# ELEKTRA-PMIC_v0_1-20240112.net
KiCad netlist of a schematic drawn in EAGLE
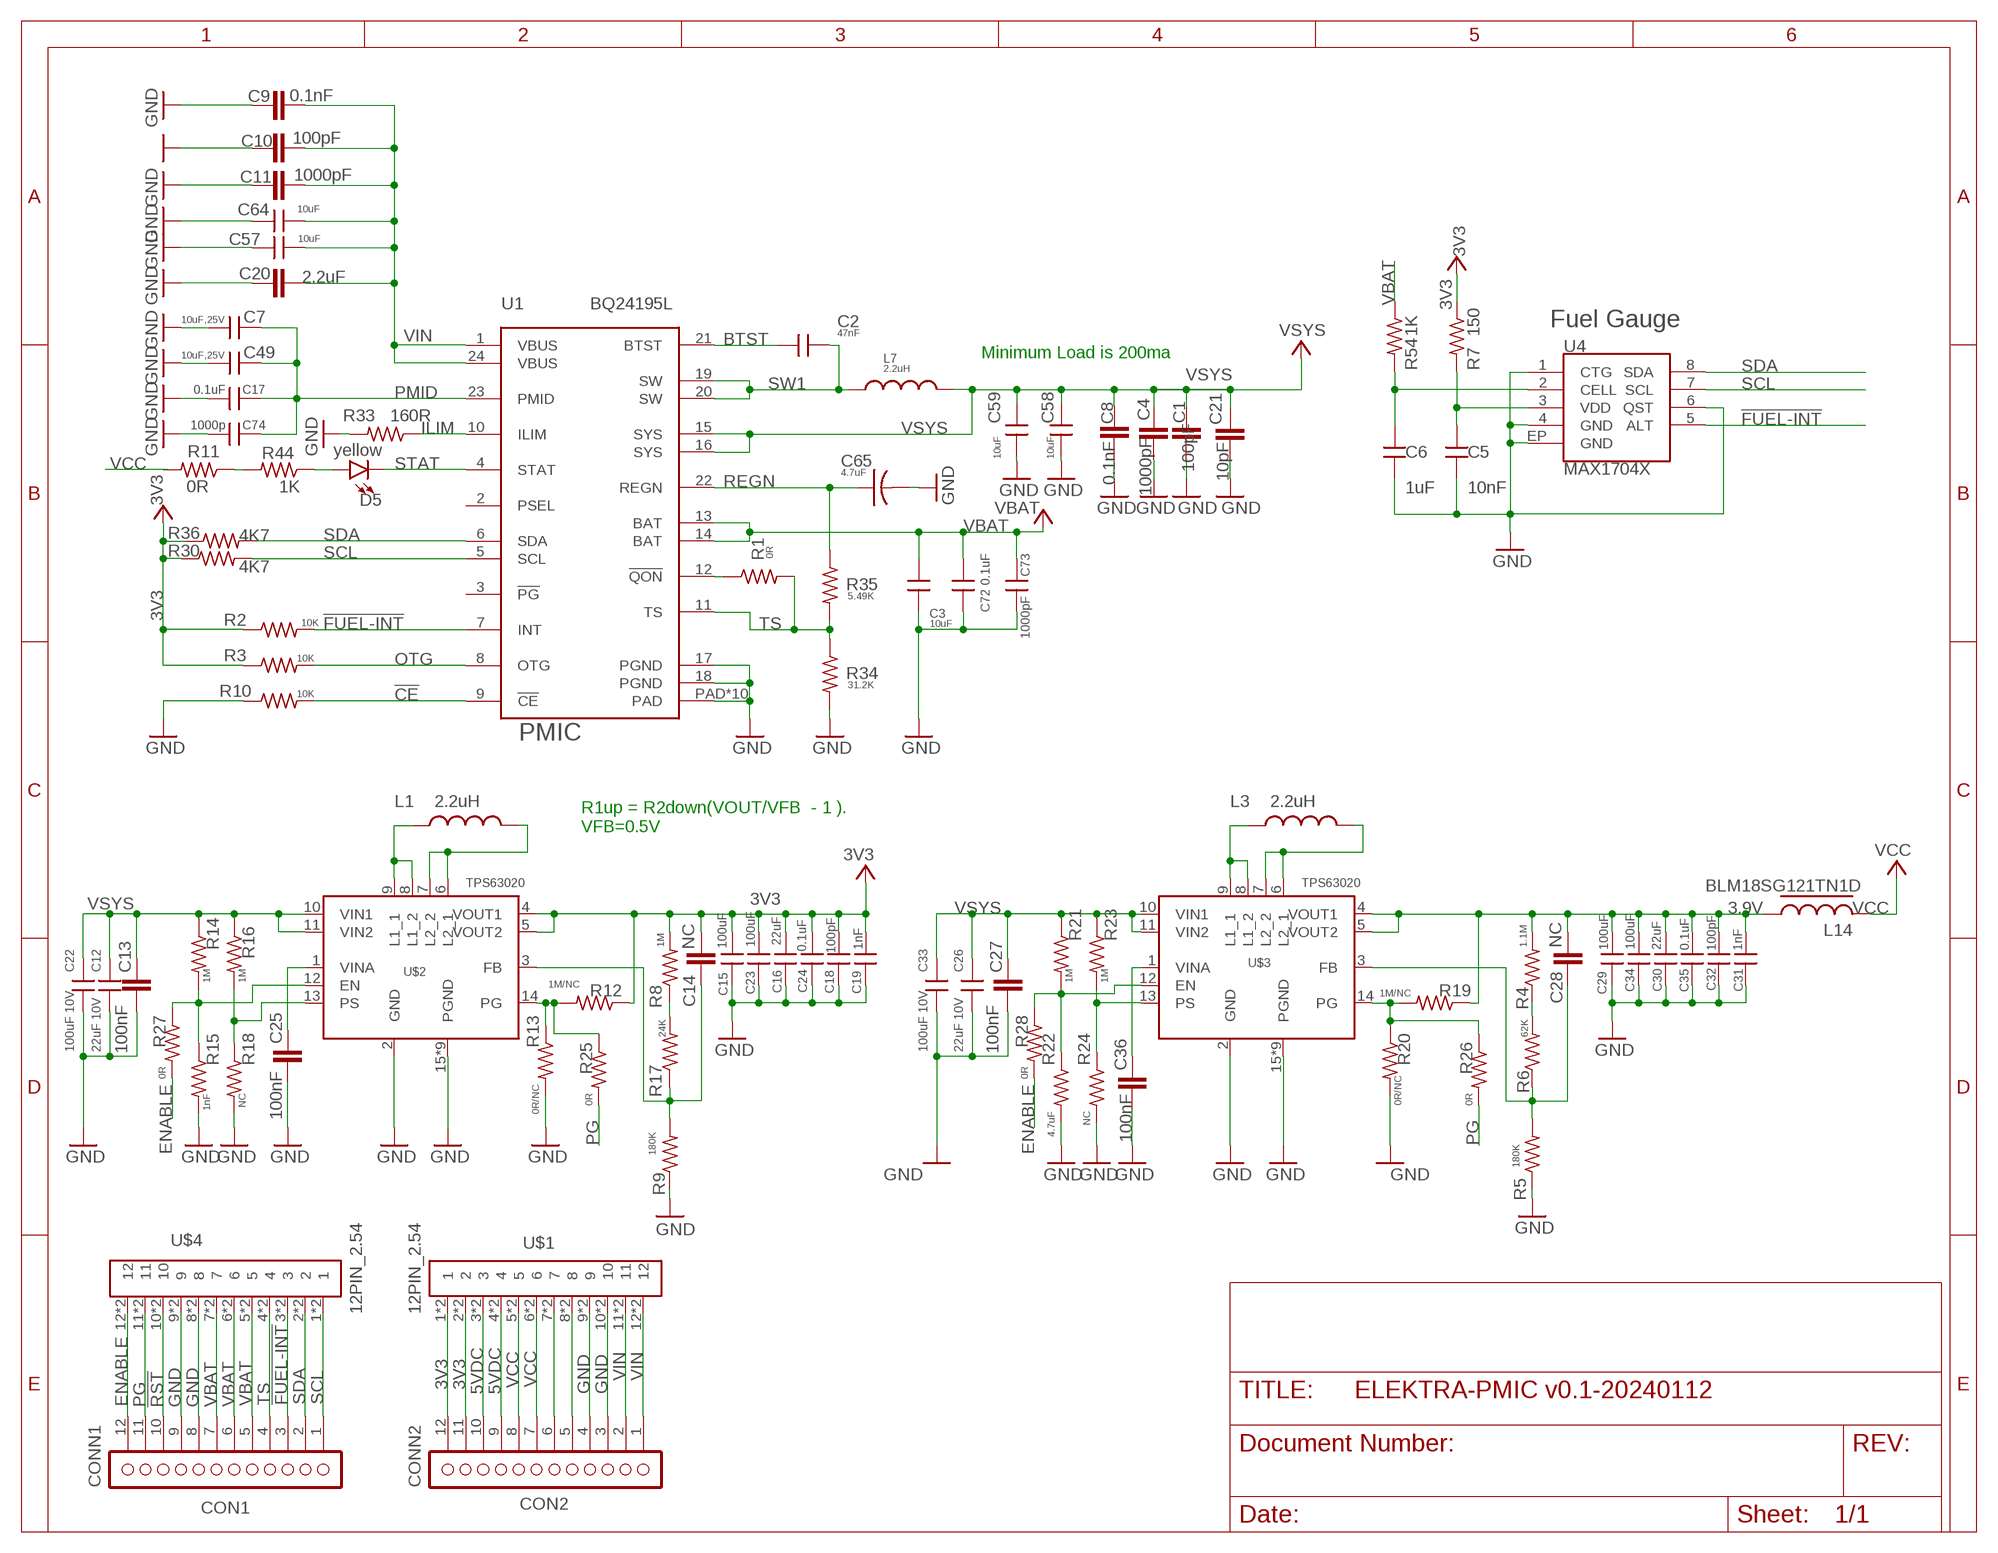
[diagram p0: schematic, sheet 1]

(export (version "E")
  (design (tool "Eeschema 10.0.6"))
  (components
    (comp (ref "C1")
      (value "100pF")
      (footprint "eagle-import:C0402_B")
      (libsource (lib "eagle-import") (part "CAP_1"))
    )
    (comp (ref "C2")
      (value "47nF")
      (footprint "eagle-import:C-0402")
      (libsource (lib "eagle-import") (part "particle SZ_CAP0402"))
    )
    (comp (ref "C3")
      (value "10uF")
      (footprint "eagle-import:C0603")
      (libsource (lib "eagle-import") (part "particle SZ_CAPC0603"))
    )
    (comp (ref "C4")
      (value "1000pF")
      (footprint "eagle-import:C0402_B")
      (libsource (lib "eagle-import") (part "CAP_1"))
    )
    (comp (ref "C5")
      (value "10nF")
      (footprint "eagle-import:C0402")
      (libsource (lib "eagle-import") (part "particle SZ_CAP0402A"))
    )
    (comp (ref "C6")
      (value "1uF")
      (footprint "eagle-import:C0402")
      (libsource (lib "eagle-import") (part "particle SZ_CAP0402A"))
    )
    (comp (ref "C7")
      (value "10uF,25V")
      (footprint "eagle-import:C-0603A")
      (libsource (lib "eagle-import") (part "particle SZ_CAP0603A"))
    )
    (comp (ref "C8")
      (value "0.1nF")
      (footprint "eagle-import:C0402_B")
      (libsource (lib "eagle-import") (part "CAP_1"))
    )
    (comp (ref "C9")
      (value "0.1nF")
      (footprint "eagle-import:C0402_B")
      (libsource (lib "eagle-import") (part "CAP_1"))
    )
    (comp (ref "C10")
      (value "100pF")
      (footprint "eagle-import:C0402_B")
      (libsource (lib "eagle-import") (part "CAP_1"))
    )
    (comp (ref "C11")
      (value "1000pF")
      (footprint "eagle-import:C0402_B")
      (libsource (lib "eagle-import") (part "CAP_1"))
    )
    (comp (ref "C12")
      (value "22uF 10V")
      (footprint "eagle-import:C0805")
      (libsource (lib "eagle-import") (part "particle SZ_21650216_CAPC0805"))
    )
    (comp (ref "C13")
      (value "100nF")
      (footprint "eagle-import:C0402_B")
      (libsource (lib "eagle-import") (part "CAP_1"))
    )
    (comp (ref "C14")
      (value "NC")
      (footprint "eagle-import:C0402_B")
      (libsource (lib "eagle-import") (part "CAP_1"))
    )
    (comp (ref "C15")
      (value "100uF")
      (footprint "eagle-import:C1206")
      (libsource (lib "eagle-import") (part "particle SZ_21650216_CAPC1206"))
    )
    (comp (ref "C16")
      (value "22uF")
      (footprint "eagle-import:C-0603A")
      (libsource (lib "eagle-import") (part "particle SZ_21650216_CAP0603A"))
    )
    (comp (ref "C17")
      (value "0.1uF")
      (footprint "eagle-import:C0402")
      (libsource (lib "eagle-import") (part "CAP0402A"))
    )
    (comp (ref "C18")
      (value "100pF")
      (footprint "eagle-import:C0402")
      (libsource (lib "eagle-import") (part "particle SZ_CAP0402A"))
    )
    (comp (ref "C19")
      (value "1nF")
      (footprint "eagle-import:C0402")
      (libsource (lib "eagle-import") (part "particle SZ_CAP0402A"))
    )
    (comp (ref "C20")
      (value "2.2uF")
      (footprint "eagle-import:C0402_B")
      (libsource (lib "eagle-import") (part "CAP_1"))
    )
    (comp (ref "C21")
      (value "10pF")
      (footprint "eagle-import:C0402_B")
      (libsource (lib "eagle-import") (part "CAP_1"))
    )
    (comp (ref "C22")
      (value "100uF 10V")
      (footprint "eagle-import:C1206")
      (libsource (lib "eagle-import") (part "particle SZ_21650216_CAPC1206"))
    )
    (comp (ref "C23")
      (value "100uF")
      (footprint "eagle-import:C1206")
      (libsource (lib "eagle-import") (part "particle SZ_21650216_CAPC1206"))
    )
    (comp (ref "C24")
      (value "0.1uF")
      (footprint "eagle-import:C0402")
      (libsource (lib "eagle-import") (part "particle SZ_CAP0402A"))
    )
    (comp (ref "C25")
      (value "100nF")
      (footprint "eagle-import:C0402_B")
      (libsource (lib "eagle-import") (part "CAP_1"))
    )
    (comp (ref "C26")
      (value "22uF 10V")
      (footprint "eagle-import:C0805")
      (libsource (lib "eagle-import") (part "particle SZ_21650216_CAPC0805"))
    )
    (comp (ref "C27")
      (value "100nF")
      (footprint "eagle-import:C0402_B")
      (libsource (lib "eagle-import") (part "CAP_1"))
    )
    (comp (ref "C28")
      (value "NC")
      (footprint "eagle-import:C0402_B")
      (libsource (lib "eagle-import") (part "CAP_1"))
    )
    (comp (ref "C29")
      (value "100uF")
      (footprint "eagle-import:C1206")
      (libsource (lib "eagle-import") (part "particle SZ_21650216_CAPC1206"))
    )
    (comp (ref "C30")
      (value "22uF")
      (footprint "eagle-import:C-0603A")
      (libsource (lib "eagle-import") (part "particle SZ_21650216_CAP0603A"))
    )
    (comp (ref "C31")
      (value "1nF")
      (footprint "eagle-import:C0402")
      (libsource (lib "eagle-import") (part "particle SZ_CAP0402A"))
    )
    (comp (ref "C32")
      (value "100pF")
      (footprint "eagle-import:C0402")
      (libsource (lib "eagle-import") (part "particle SZ_CAP0402A"))
    )
    (comp (ref "C33")
      (value "100uF 10V")
      (footprint "eagle-import:C1206")
      (libsource (lib "eagle-import") (part "particle SZ_21650216_CAPC1206"))
    )
    (comp (ref "C34")
      (value "100uF")
      (footprint "eagle-import:C1206")
      (libsource (lib "eagle-import") (part "particle SZ_21650216_CAPC1206"))
    )
    (comp (ref "C35")
      (value "0.1uF")
      (footprint "eagle-import:C0402")
      (libsource (lib "eagle-import") (part "particle SZ_CAP0402A"))
    )
    (comp (ref "C36")
      (value "100nF")
      (footprint "eagle-import:C0402_B")
      (libsource (lib "eagle-import") (part "CAP_1"))
    )
    (comp (ref "C49")
      (value "10uF,25V")
      (footprint "eagle-import:C-0603A")
      (libsource (lib "eagle-import") (part "particle SZ_CAP0603A"))
    )
    (comp (ref "C57")
      (value "10uF")
      (footprint "eagle-import:C-0603A")
      (libsource (lib "eagle-import") (part "particle SZ_CAP0603A"))
    )
    (comp (ref "C58")
      (value "10uF")
      (footprint "eagle-import:C-0603A")
      (libsource (lib "eagle-import") (part "particle SZ_CAP0603A"))
    )
    (comp (ref "C59")
      (value "10uF")
      (footprint "eagle-import:C-0603A")
      (libsource (lib "eagle-import") (part "particle SZ_CAP0603A"))
    )
    (comp (ref "C64")
      (value "10uF")
      (footprint "eagle-import:C-0603A")
      (libsource (lib "eagle-import") (part "particle SZ_CAP0603A"))
    )
    (comp (ref "C65")
      (value "4.7uF")
      (footprint "eagle-import:C0603_B")
      (libsource (lib "eagle-import") (part "C-US0603"))
    )
    (comp (ref "C72")
      (value "0.1uF")
      (footprint "eagle-import:C-0402")
      (libsource (lib "eagle-import") (part "particle SZ_CAP0402"))
    )
    (comp (ref "C73")
      (value "1000pF")
      (footprint "eagle-import:C-0402")
      (libsource (lib "eagle-import") (part "particle SZ_CAP0402"))
    )
    (comp (ref "C74")
      (value "1000p")
      (footprint "eagle-import:C-0402")
      (libsource (lib "eagle-import") (part "particle SZ_CAP0402"))
    )
    (comp (ref "CONN1")
      (value "CON1")
      (footprint "eagle-import:1X12_SMD_STRAIGHT")
      (libsource (lib "eagle-import") (part "CONN12"))
    )
    (comp (ref "CONN2")
      (value "CON2")
      (footprint "eagle-import:1X12_SMD_STRAIGHT")
      (libsource (lib "eagle-import") (part "CONN12"))
    )
    (comp (ref "D5")
      (value "yellow")
      (footprint "eagle-import:LED-0603")
      (libsource (lib "eagle-import") (part "LED-RED0603"))
    )
    (comp (ref "L1")
      (value "2.2uH")
      (footprint "eagle-import:INDUCTOR-VLS-E")
      (libsource (lib "eagle-import") (part "INDUCTOR-SPARKFUNVLS3012ET-4R7M"))
    )
    (comp (ref "L3")
      (value "2.2uH")
      (footprint "eagle-import:INDUCTOR-VLS-E")
      (libsource (lib "eagle-import") (part "INDUCTOR-SPARKFUNVLS3012ET-4R7M"))
    )
    (comp (ref "L7")
      (value "2.2uH")
      (footprint "eagle-import:INDUCTOR-4040")
      (libsource (lib "eagle-import") (part "INDUCTORI"))
    )
    (comp (ref "L14")
      (value "BLM18SG121TN1D")
      (footprint "eagle-import:R-0603A")
      (libsource (lib "eagle-import") (part "L"))
    )
    (comp (ref "R1")
      (value "0R")
      (footprint "eagle-import:R0402_B")
      (libsource (lib "eagle-import") (part "Spark_R-US_"))
    )
    (comp (ref "R2")
      (value "10K")
      (footprint "eagle-import:R0402_B")
      (libsource (lib "eagle-import") (part "Spark_R-US_"))
    )
    (comp (ref "R3")
      (value "10K")
      (footprint "eagle-import:R0402_B")
      (libsource (lib "eagle-import") (part "Spark_R-US_"))
    )
    (comp (ref "R4")
      (value "1.1M")
      (footprint "eagle-import:R0402_B")
      (libsource (lib "eagle-import") (part "Spark_R-US_"))
    )
    (comp (ref "R5")
      (value "180K")
      (footprint "eagle-import:R0402_B")
      (libsource (lib "eagle-import") (part "Spark_R-US_"))
    )
    (comp (ref "R6")
      (value "62K")
      (footprint "eagle-import:R0402_B")
      (libsource (lib "eagle-import") (part "Spark_R-US_"))
    )
    (comp (ref "R7")
      (value "150")
      (footprint "eagle-import:R0402_B")
      (libsource (lib "eagle-import") (part "R-US_"))
    )
    (comp (ref "R8")
      (value "1M")
      (footprint "eagle-import:R0402_B")
      (libsource (lib "eagle-import") (part "Spark_R-US_"))
    )
    (comp (ref "R9")
      (value "180K")
      (footprint "eagle-import:R0402_B")
      (libsource (lib "eagle-import") (part "Spark_R-US_"))
    )
    (comp (ref "R10")
      (value "10K")
      (footprint "eagle-import:R0402_B")
      (libsource (lib "eagle-import") (part "Spark_R-US_"))
    )
    (comp (ref "R11")
      (value "0R")
      (footprint "eagle-import:R0402_B")
      (libsource (lib "eagle-import") (part "R-US_"))
    )
    (comp (ref "R12")
      (value "1M/NC")
      (footprint "eagle-import:R0402_B")
      (libsource (lib "eagle-import") (part "Spark_R-US_"))
    )
    (comp (ref "R13")
      (value "0R/NC")
      (footprint "eagle-import:R0402_B")
      (libsource (lib "eagle-import") (part "Spark_R-US_"))
    )
    (comp (ref "R14")
      (value "1M")
      (footprint "eagle-import:R0402_B")
      (libsource (lib "eagle-import") (part "Spark_R-US_"))
    )
    (comp (ref "R15")
      (value "1nF")
      (footprint "eagle-import:R0402_B")
      (libsource (lib "eagle-import") (part "Spark_R-US_"))
    )
    (comp (ref "R16")
      (value "1M")
      (footprint "eagle-import:R0402_B")
      (libsource (lib "eagle-import") (part "Spark_R-US_"))
    )
    (comp (ref "R17")
      (value "24K")
      (footprint "eagle-import:R0402_B")
      (libsource (lib "eagle-import") (part "Spark_R-US_"))
    )
    (comp (ref "R18")
      (value "NC")
      (footprint "eagle-import:R0402_B")
      (libsource (lib "eagle-import") (part "Spark_R-US_"))
    )
    (comp (ref "R19")
      (value "1M/NC")
      (footprint "eagle-import:R0402_B")
      (libsource (lib "eagle-import") (part "Spark_R-US_"))
    )
    (comp (ref "R20")
      (value "0R/NC")
      (footprint "eagle-import:R0402_B")
      (libsource (lib "eagle-import") (part "Spark_R-US_"))
    )
    (comp (ref "R21")
      (value "1M")
      (footprint "eagle-import:R0402_B")
      (libsource (lib "eagle-import") (part "Spark_R-US_"))
    )
    (comp (ref "R22")
      (value "4.7uF")
      (footprint "eagle-import:R0402_B")
      (libsource (lib "eagle-import") (part "Spark_R-US_"))
    )
    (comp (ref "R23")
      (value "1M")
      (footprint "eagle-import:R0402_B")
      (libsource (lib "eagle-import") (part "Spark_R-US_"))
    )
    (comp (ref "R24")
      (value "NC")
      (footprint "eagle-import:R0402_B")
      (libsource (lib "eagle-import") (part "Spark_R-US_"))
    )
    (comp (ref "R25")
      (value "0R")
      (footprint "eagle-import:R0402_B")
      (libsource (lib "eagle-import") (part "Spark_R-US_"))
    )
    (comp (ref "R26")
      (value "0R")
      (footprint "eagle-import:R0402_B")
      (libsource (lib "eagle-import") (part "Spark_R-US_"))
    )
    (comp (ref "R27")
      (value "0R")
      (footprint "eagle-import:R0402_B")
      (libsource (lib "eagle-import") (part "Spark_R-US_"))
    )
    (comp (ref "R28")
      (value "0R")
      (footprint "eagle-import:R0402_B")
      (libsource (lib "eagle-import") (part "Spark_R-US_"))
    )
    (comp (ref "R30")
      (value "4K7")
      (footprint "eagle-import:R0402_B")
      (libsource (lib "eagle-import") (part "R-US_"))
    )
    (comp (ref "R33")
      (value "160R")
      (footprint "eagle-import:R0402_B")
      (libsource (lib "eagle-import") (part "R-US_"))
    )
    (comp (ref "R34")
      (value "31.2K")
      (footprint "eagle-import:R0402_B")
      (libsource (lib "eagle-import") (part "Spark_R-US_"))
    )
    (comp (ref "R35")
      (value "5.49K")
      (footprint "eagle-import:R0402_B")
      (libsource (lib "eagle-import") (part "Spark_R-US_"))
    )
    (comp (ref "R36")
      (value "4K7")
      (footprint "eagle-import:R0402_B")
      (libsource (lib "eagle-import") (part "R-US_"))
    )
    (comp (ref "R44")
      (value "1K")
      (footprint "eagle-import:R0402_B")
      (libsource (lib "eagle-import") (part "R-US_"))
    )
    (comp (ref "R54")
      (value "1K")
      (footprint "eagle-import:R0402_B")
      (libsource (lib "eagle-import") (part "R-US_"))
    )
    (comp (ref "U$1")
      (value "12PIN_2.54")
      (footprint "eagle-import:12PIN_2.54")
      (libsource (lib "eagle-import") (part "12PIN_2.54"))
    )
    (comp (ref "U$2")
      (value "TPS63020")
      (footprint "eagle-import:TPS63020")
      (libsource (lib "eagle-import") (part "TPS63020"))
    )
    (comp (ref "U$3")
      (value "TPS63020")
      (footprint "eagle-import:TPS63020")
      (libsource (lib "eagle-import") (part "TPS63020"))
    )
    (comp (ref "U$4")
      (value "12PIN_2.54")
      (footprint "eagle-import:12PIN_2.54")
      (libsource (lib "eagle-import") (part "12PIN_2.54"))
    )
    (comp (ref "U1")
      (value "BQ24195L")
      (footprint "eagle-import:QFN24")
      (libsource (lib "eagle-import") (part "BQ24298RTWR"))
    )
    (comp (ref "U4")
      (value "MAX1704X")
      (footprint "eagle-import:TDFN-8")
      (libsource (lib "eagle-import") (part "MAX1704X"))
    )
  )
  (nets
    (net (code "1") (name "/3.9V") (class "Default")
      (node (ref "C28") (pin "2") (pinfunction "P$2_2") (pintype "passive"))
      (node (ref "C29") (pin "1") (pinfunction "1_1") (pintype "bidirectional"))
      (node (ref "C30") (pin "1") (pinfunction "1_1") (pintype "bidirectional"))
      (node (ref "C31") (pin "1") (pinfunction "1_1") (pintype "bidirectional"))
      (node (ref "C32") (pin "1") (pinfunction "1_1") (pintype "bidirectional"))
      (node (ref "C34") (pin "1") (pinfunction "1_1") (pintype "bidirectional"))
      (node (ref "C35") (pin "1") (pinfunction "1_1") (pintype "bidirectional"))
      (node (ref "L14") (pin "2") (pinfunction "2_2") (pintype "bidirectional"))
      (node (ref "R19") (pin "1") (pinfunction "1_1") (pintype "passive"))
      (node (ref "R4") (pin "2") (pinfunction "2_2") (pintype "passive"))
      (node (ref "U$3") (pin "4") (pinfunction "VOUT1_4") (pintype "bidirectional"))
      (node (ref "U$3") (pin "5") (pinfunction "VOUT2_5") (pintype "bidirectional"))
    )
    (net (code "2") (name "/5VDC") (class "Default")
      (node (ref "CONN2") (pin "10") (pinfunction "10_10") (pintype "passive"))
      (node (ref "CONN2") (pin "9") (pinfunction "9_9") (pintype "passive"))
      (node (ref "U$1") (pin "3") (pinfunction "3_3") (pintype "bidirectional"))
      (node (ref "U$1") (pin "4") (pinfunction "4_4") (pintype "bidirectional"))
      (node (ref "U$1") (pin "P$3") (pinfunction "3_P$3") (pintype "bidirectional"))
      (node (ref "U$1") (pin "P$4") (pinfunction "4_P$4") (pintype "bidirectional"))
    )
    (net (code "3") (name "/BTST") (class "Default")
      (node (ref "C2") (pin "1") (pinfunction "1_1") (pintype "bidirectional"))
      (node (ref "U1") (pin "21") (pinfunction "BTST_21") (pintype "bidirectional"))
    )
    (net (code "4") (name "/ENABLE") (class "Default")
      (node (ref "CONN1") (pin "12") (pinfunction "12_12") (pintype "passive"))
      (node (ref "R27") (pin "2") (pinfunction "2_2") (pintype "passive"))
      (node (ref "R28") (pin "2") (pinfunction "2_2") (pintype "passive"))
      (node (ref "U$4") (pin "12") (pinfunction "12_12") (pintype "bidirectional"))
      (node (ref "U$4") (pin "P$12") (pinfunction "12_P$12") (pintype "bidirectional"))
    )
    (net (code "5") (name "/ILIM") (class "Default")
      (node (ref "R33") (pin "1") (pinfunction "1_1") (pintype "passive"))
      (node (ref "U1") (pin "10") (pinfunction "ILIM_10") (pintype "output"))
    )
    (net (code "6") (name "/OTG") (class "Default")
      (node (ref "R3") (pin "2") (pinfunction "2_2") (pintype "passive"))
      (node (ref "U1") (pin "8") (pinfunction "OTG_8") (pintype "bidirectional"))
    )
    (net (code "7") (name "/PG") (class "Default")
      (node (ref "CONN1") (pin "11") (pinfunction "11_11") (pintype "passive"))
      (node (ref "R25") (pin "2") (pinfunction "2_2") (pintype "passive"))
      (node (ref "R26") (pin "2") (pinfunction "2_2") (pintype "passive"))
      (node (ref "U$4") (pin "11") (pinfunction "11_11") (pintype "bidirectional"))
      (node (ref "U$4") (pin "P$11") (pinfunction "11_P$11") (pintype "bidirectional"))
    )
    (net (code "8") (name "/PMID") (class "Default")
      (node (ref "C17") (pin "2") (pinfunction "2_2") (pintype "bidirectional"))
      (node (ref "C49") (pin "1") (pinfunction "1_1") (pintype "bidirectional"))
      (node (ref "C7") (pin "1") (pinfunction "1_1") (pintype "bidirectional"))
      (node (ref "C74") (pin "2") (pinfunction "2_2") (pintype "bidirectional"))
      (node (ref "U1") (pin "23") (pinfunction "PMID_23") (pintype "passive"))
    )
    (net (code "9") (name "/REGN") (class "Default")
      (node (ref "C65") (pin "1") (pinfunction "1_1") (pintype "passive"))
      (node (ref "R35") (pin "1") (pinfunction "1_1") (pintype "passive"))
      (node (ref "U1") (pin "22") (pinfunction "REGN_22") (pintype "bidirectional"))
    )
    (net (code "10") (name "/SCL") (class "Default")
      (node (ref "CONN1") (pin "1") (pinfunction "1_1") (pintype "passive"))
      (node (ref "R30") (pin "2") (pinfunction "2_2") (pintype "passive"))
      (node (ref "U$4") (pin "1") (pinfunction "1_1") (pintype "bidirectional"))
      (node (ref "U$4") (pin "P$1") (pinfunction "1_P$1") (pintype "bidirectional"))
      (node (ref "U1") (pin "5") (pinfunction "SCL_5") (pintype "output"))
      (node (ref "U4") (pin "7") (pinfunction "SCL_7") (pintype "bidirectional"))
    )
    (net (code "11") (name "/SDA") (class "Default")
      (node (ref "CONN1") (pin "2") (pinfunction "2_2") (pintype "passive"))
      (node (ref "R36") (pin "2") (pinfunction "2_2") (pintype "passive"))
      (node (ref "U$4") (pin "2") (pinfunction "2_2") (pintype "bidirectional"))
      (node (ref "U$4") (pin "P$2") (pinfunction "2_P$2") (pintype "bidirectional"))
      (node (ref "U1") (pin "6") (pinfunction "SDA_6") (pintype "bidirectional"))
      (node (ref "U4") (pin "8") (pinfunction "SDA_8") (pintype "bidirectional"))
    )
    (net (code "12") (name "/STAT") (class "Default")
      (node (ref "D5") (pin "C") (pinfunction "C_C") (pintype "passive"))
      (node (ref "U1") (pin "4") (pinfunction "STAT_4") (pintype "bidirectional"))
    )
    (net (code "13") (name "/SW1") (class "Default")
      (node (ref "C2") (pin "2") (pinfunction "2_2") (pintype "bidirectional"))
      (node (ref "L7") (pin "P$1") (pinfunction "1_P$1") (pintype "passive"))
      (node (ref "U1") (pin "19") (pinfunction "SW_19") (pintype "power_in"))
      (node (ref "U1") (pin "20") (pinfunction "SW_20") (pintype "power_in"))
    )
    (net (code "14") (name "/TS") (class "Default")
      (node (ref "CONN1") (pin "4") (pinfunction "4_4") (pintype "passive"))
      (node (ref "R1") (pin "2") (pinfunction "2_2") (pintype "passive"))
      (node (ref "R34") (pin "1") (pinfunction "1_1") (pintype "passive"))
      (node (ref "R35") (pin "2") (pinfunction "2_2") (pintype "passive"))
      (node (ref "U$4") (pin "4") (pinfunction "4_4") (pintype "bidirectional"))
      (node (ref "U$4") (pin "P$4") (pinfunction "4_P$4") (pintype "bidirectional"))
      (node (ref "U1") (pin "11") (pinfunction "TS_11") (pintype "bidirectional"))
    )
    (net (code "15") (name "/VIN") (class "Default")
      (node (ref "C10") (pin "2") (pinfunction "P$2_2") (pintype "passive"))
      (node (ref "C11") (pin "2") (pinfunction "P$2_2") (pintype "passive"))
      (node (ref "C20") (pin "2") (pinfunction "P$2_2") (pintype "passive"))
      (node (ref "C57") (pin "1") (pinfunction "1_1") (pintype "bidirectional"))
      (node (ref "C64") (pin "1") (pinfunction "1_1") (pintype "bidirectional"))
      (node (ref "C9") (pin "2") (pinfunction "P$2_2") (pintype "passive"))
      (node (ref "CONN2") (pin "1") (pinfunction "1_1") (pintype "passive"))
      (node (ref "CONN2") (pin "2") (pinfunction "2_2") (pintype "passive"))
      (node (ref "U$1") (pin "11") (pinfunction "11_11") (pintype "bidirectional"))
      (node (ref "U$1") (pin "12") (pinfunction "12_12") (pintype "bidirectional"))
      (node (ref "U$1") (pin "P$11") (pinfunction "11_P$11") (pintype "bidirectional"))
      (node (ref "U$1") (pin "P$12") (pinfunction "12_P$12") (pintype "bidirectional"))
      (node (ref "U1") (pin "1") (pinfunction "VBUS_1") (pintype "power_in"))
      (node (ref "U1") (pin "24") (pinfunction "VBUS_24") (pintype "passive"))
    )
    (net (code "16") (name "/~{CE}") (class "Default")
      (node (ref "R10") (pin "2") (pinfunction "2_2") (pintype "passive"))
      (node (ref "U1") (pin "9") (pinfunction "~{CE}_9") (pintype "output"))
    )
    (net (code "17") (name "/~{FUEL-INT}") (class "Default")
      (node (ref "CONN1") (pin "3") (pinfunction "3_3") (pintype "passive"))
      (node (ref "R2") (pin "2") (pinfunction "2_2") (pintype "passive"))
      (node (ref "U$4") (pin "3") (pinfunction "3_3") (pintype "bidirectional"))
      (node (ref "U$4") (pin "P$3") (pinfunction "3_P$3") (pintype "bidirectional"))
      (node (ref "U1") (pin "7") (pinfunction "INT_7") (pintype "bidirectional"))
      (node (ref "U4") (pin "5") (pinfunction "ALT_5") (pintype "bidirectional"))
    )
    (net (code "18") (name "/~{RST}") (class "Default")
      (node (ref "CONN1") (pin "10") (pinfunction "10_10") (pintype "passive"))
      (node (ref "U$4") (pin "10") (pinfunction "10_10") (pintype "bidirectional"))
      (node (ref "U$4") (pin "P$10") (pinfunction "10_P$10") (pintype "bidirectional"))
    )
    (net (code "19") (name "3V3") (class "Default")
      (node (ref "C14") (pin "2") (pinfunction "P$2_2") (pintype "passive"))
      (node (ref "C15") (pin "1") (pinfunction "1_1") (pintype "bidirectional"))
      (node (ref "C16") (pin "1") (pinfunction "1_1") (pintype "bidirectional"))
      (node (ref "C18") (pin "1") (pinfunction "1_1") (pintype "bidirectional"))
      (node (ref "C19") (pin "1") (pinfunction "1_1") (pintype "bidirectional"))
      (node (ref "C23") (pin "1") (pinfunction "1_1") (pintype "bidirectional"))
      (node (ref "C24") (pin "1") (pinfunction "1_1") (pintype "bidirectional"))
      (node (ref "CONN2") (pin "11") (pinfunction "11_11") (pintype "passive"))
      (node (ref "CONN2") (pin "12") (pinfunction "12_12") (pintype "passive"))
      (node (ref "R12") (pin "1") (pinfunction "1_1") (pintype "passive"))
      (node (ref "R2") (pin "1") (pinfunction "1_1") (pintype "passive"))
      (node (ref "R3") (pin "1") (pinfunction "1_1") (pintype "passive"))
      (node (ref "R30") (pin "1") (pinfunction "1_1") (pintype "passive"))
      (node (ref "R36") (pin "1") (pinfunction "1_1") (pintype "passive"))
      (node (ref "R7") (pin "1") (pinfunction "1_1") (pintype "passive"))
      (node (ref "R8") (pin "2") (pinfunction "2_2") (pintype "passive"))
      (node (ref "U$1") (pin "1") (pinfunction "1_1") (pintype "bidirectional"))
      (node (ref "U$1") (pin "2") (pinfunction "2_2") (pintype "bidirectional"))
      (node (ref "U$1") (pin "P$1") (pinfunction "1_P$1") (pintype "bidirectional"))
      (node (ref "U$1") (pin "P$2") (pinfunction "2_P$2") (pintype "bidirectional"))
      (node (ref "U$2") (pin "4") (pinfunction "VOUT1_4") (pintype "bidirectional"))
      (node (ref "U$2") (pin "5") (pinfunction "VOUT2_5") (pintype "bidirectional"))
    )
    (net (code "20") (name "GND") (class "Default")
      (node (ref "C1") (pin "1") (pinfunction "P$1_1") (pintype "passive"))
      (node (ref "C10") (pin "1") (pinfunction "P$1_1") (pintype "passive"))
      (node (ref "C11") (pin "1") (pinfunction "P$1_1") (pintype "passive"))
      (node (ref "C12") (pin "2") (pinfunction "2_2") (pintype "bidirectional"))
      (node (ref "C13") (pin "1") (pinfunction "P$1_1") (pintype "passive"))
      (node (ref "C15") (pin "2") (pinfunction "2_2") (pintype "bidirectional"))
      (node (ref "C16") (pin "2") (pinfunction "2_2") (pintype "bidirectional"))
      (node (ref "C17") (pin "1") (pinfunction "1_1") (pintype "bidirectional"))
      (node (ref "C18") (pin "2") (pinfunction "2_2") (pintype "bidirectional"))
      (node (ref "C19") (pin "2") (pinfunction "2_2") (pintype "bidirectional"))
      (node (ref "C20") (pin "1") (pinfunction "P$1_1") (pintype "passive"))
      (node (ref "C21") (pin "1") (pinfunction "P$1_1") (pintype "passive"))
      (node (ref "C22") (pin "2") (pinfunction "2_2") (pintype "bidirectional"))
      (node (ref "C23") (pin "2") (pinfunction "2_2") (pintype "bidirectional"))
      (node (ref "C24") (pin "2") (pinfunction "2_2") (pintype "bidirectional"))
      (node (ref "C25") (pin "1") (pinfunction "P$1_1") (pintype "passive"))
      (node (ref "C26") (pin "2") (pinfunction "2_2") (pintype "bidirectional"))
      (node (ref "C27") (pin "1") (pinfunction "P$1_1") (pintype "passive"))
      (node (ref "C29") (pin "2") (pinfunction "2_2") (pintype "bidirectional"))
      (node (ref "C3") (pin "2") (pinfunction "2_2") (pintype "bidirectional"))
      (node (ref "C30") (pin "2") (pinfunction "2_2") (pintype "bidirectional"))
      (node (ref "C31") (pin "2") (pinfunction "2_2") (pintype "bidirectional"))
      (node (ref "C32") (pin "2") (pinfunction "2_2") (pintype "bidirectional"))
      (node (ref "C33") (pin "2") (pinfunction "2_2") (pintype "bidirectional"))
      (node (ref "C34") (pin "2") (pinfunction "2_2") (pintype "bidirectional"))
      (node (ref "C35") (pin "2") (pinfunction "2_2") (pintype "bidirectional"))
      (node (ref "C36") (pin "1") (pinfunction "P$1_1") (pintype "passive"))
      (node (ref "C4") (pin "1") (pinfunction "P$1_1") (pintype "passive"))
      (node (ref "C49") (pin "2") (pinfunction "2_2") (pintype "bidirectional"))
      (node (ref "C5") (pin "2") (pinfunction "2_2") (pintype "bidirectional"))
      (node (ref "C57") (pin "2") (pinfunction "2_2") (pintype "bidirectional"))
      (node (ref "C58") (pin "2") (pinfunction "2_2") (pintype "bidirectional"))
      (node (ref "C59") (pin "2") (pinfunction "2_2") (pintype "bidirectional"))
      (node (ref "C6") (pin "2") (pinfunction "2_2") (pintype "bidirectional"))
      (node (ref "C64") (pin "2") (pinfunction "2_2") (pintype "bidirectional"))
      (node (ref "C65") (pin "2") (pinfunction "2_2") (pintype "passive"))
      (node (ref "C7") (pin "2") (pinfunction "2_2") (pintype "bidirectional"))
      (node (ref "C72") (pin "2") (pinfunction "2_2") (pintype "bidirectional"))
      (node (ref "C73") (pin "2") (pinfunction "2_2") (pintype "bidirectional"))
      (node (ref "C74") (pin "1") (pinfunction "1_1") (pintype "bidirectional"))
      (node (ref "C8") (pin "1") (pinfunction "P$1_1") (pintype "passive"))
      (node (ref "C9") (pin "1") (pinfunction "P$1_1") (pintype "passive"))
      (node (ref "CONN1") (pin "8") (pinfunction "8_8") (pintype "passive"))
      (node (ref "CONN1") (pin "9") (pinfunction "9_9") (pintype "passive"))
      (node (ref "CONN2") (pin "3") (pinfunction "3_3") (pintype "passive"))
      (node (ref "CONN2") (pin "4") (pinfunction "4_4") (pintype "passive"))
      (node (ref "R10") (pin "1") (pinfunction "1_1") (pintype "passive"))
      (node (ref "R13") (pin "2") (pinfunction "2_2") (pintype "passive"))
      (node (ref "R15") (pin "2") (pinfunction "2_2") (pintype "passive"))
      (node (ref "R18") (pin "2") (pinfunction "2_2") (pintype "passive"))
      (node (ref "R20") (pin "2") (pinfunction "2_2") (pintype "passive"))
      (node (ref "R22") (pin "2") (pinfunction "2_2") (pintype "passive"))
      (node (ref "R24") (pin "2") (pinfunction "2_2") (pintype "passive"))
      (node (ref "R33") (pin "2") (pinfunction "2_2") (pintype "passive"))
      (node (ref "R34") (pin "2") (pinfunction "2_2") (pintype "passive"))
      (node (ref "R5") (pin "1") (pinfunction "1_1") (pintype "passive"))
      (node (ref "R9") (pin "1") (pinfunction "1_1") (pintype "passive"))
      (node (ref "U$1") (pin "10") (pinfunction "10_10") (pintype "bidirectional"))
      (node (ref "U$1") (pin "9") (pinfunction "9_9") (pintype "bidirectional"))
      (node (ref "U$1") (pin "P$10") (pinfunction "10_P$10") (pintype "bidirectional"))
      (node (ref "U$1") (pin "P$9") (pinfunction "9_P$9") (pintype "bidirectional"))
      (node (ref "U$2") (pin "15") (pinfunction "PGND_15") (pintype "bidirectional"))
      (node (ref "U$2") (pin "16") (pinfunction "PGND_16") (pintype "bidirectional"))
      (node (ref "U$2") (pin "17") (pinfunction "PGND_17") (pintype "bidirectional"))
      (node (ref "U$2") (pin "18") (pinfunction "PGND_18") (pintype "bidirectional"))
      (node (ref "U$2") (pin "19") (pinfunction "PGND_19") (pintype "bidirectional"))
      (node (ref "U$2") (pin "2") (pinfunction "GND_2") (pintype "bidirectional"))
      (node (ref "U$2") (pin "20") (pinfunction "PGND_20") (pintype "bidirectional"))
      (node (ref "U$2") (pin "21") (pinfunction "PGND_21") (pintype "bidirectional"))
      (node (ref "U$2") (pin "22") (pinfunction "PGND_22") (pintype "bidirectional"))
      (node (ref "U$2") (pin "23") (pinfunction "PGND_23") (pintype "bidirectional"))
      (node (ref "U$3") (pin "15") (pinfunction "PGND_15") (pintype "bidirectional"))
      (node (ref "U$3") (pin "16") (pinfunction "PGND_16") (pintype "bidirectional"))
      (node (ref "U$3") (pin "17") (pinfunction "PGND_17") (pintype "bidirectional"))
      (node (ref "U$3") (pin "18") (pinfunction "PGND_18") (pintype "bidirectional"))
      (node (ref "U$3") (pin "19") (pinfunction "PGND_19") (pintype "bidirectional"))
      (node (ref "U$3") (pin "2") (pinfunction "GND_2") (pintype "bidirectional"))
      (node (ref "U$3") (pin "20") (pinfunction "PGND_20") (pintype "bidirectional"))
      (node (ref "U$3") (pin "21") (pinfunction "PGND_21") (pintype "bidirectional"))
      (node (ref "U$3") (pin "22") (pinfunction "PGND_22") (pintype "bidirectional"))
      (node (ref "U$3") (pin "23") (pinfunction "PGND_23") (pintype "bidirectional"))
      (node (ref "U$4") (pin "8") (pinfunction "8_8") (pintype "bidirectional"))
      (node (ref "U$4") (pin "9") (pinfunction "9_9") (pintype "bidirectional"))
      (node (ref "U$4") (pin "P$8") (pinfunction "8_P$8") (pintype "bidirectional"))
      (node (ref "U$4") (pin "P$9") (pinfunction "9_P$9") (pintype "bidirectional"))
      (node (ref "U1") (pin "17") (pinfunction "PGND_17") (pintype "passive"))
      (node (ref "U1") (pin "18") (pinfunction "PGND_18") (pintype "passive"))
      (node (ref "U1") (pin "PAD") (pinfunction "PAD_PAD") (pintype "power_in"))
      (node (ref "U1") (pin "PAD@1") (pinfunction "PAD_PAD@1") (pintype "power_in"))
      (node (ref "U1") (pin "PAD@2") (pinfunction "PAD_PAD@2") (pintype "power_in"))
      (node (ref "U1") (pin "PAD@3") (pinfunction "PAD_PAD@3") (pintype "power_in"))
      (node (ref "U1") (pin "PAD@4") (pinfunction "PAD_PAD@4") (pintype "power_in"))
      (node (ref "U1") (pin "PAD@5") (pinfunction "PAD_PAD@5") (pintype "power_in"))
      (node (ref "U1") (pin "PAD@6") (pinfunction "PAD_PAD@6") (pintype "power_in"))
      (node (ref "U1") (pin "PAD@7") (pinfunction "PAD_PAD@7") (pintype "power_in"))
      (node (ref "U1") (pin "PAD@8") (pinfunction "PAD_PAD@8") (pintype "power_in"))
      (node (ref "U1") (pin "PAD@9") (pinfunction "PAD_PAD@9") (pintype "power_in"))
      (node (ref "U4") (pin "1") (pinfunction "CTG_1") (pintype "bidirectional"))
      (node (ref "U4") (pin "4") (pinfunction "GND_4") (pintype "bidirectional"))
      (node (ref "U4") (pin "6") (pinfunction "QST_6") (pintype "bidirectional"))
      (node (ref "U4") (pin "EP") (pinfunction "GND_EP") (pintype "bidirectional"))
    )
    (net (code "21") (name "Net-(C14-P$1)") (class "Default")
      (node (ref "C14") (pin "1") (pinfunction "P$1_1") (pintype "passive"))
      (node (ref "R17") (pin "1") (pinfunction "1_1") (pintype "passive"))
      (node (ref "R9") (pin "2") (pinfunction "2_2") (pintype "passive"))
      (node (ref "U$2") (pin "3") (pinfunction "FB_3") (pintype "bidirectional"))
    )
    (net (code "22") (name "Net-(C25-P$2)") (class "Default")
      (node (ref "C25") (pin "2") (pinfunction "P$2_2") (pintype "passive"))
      (node (ref "U$2") (pin "1") (pinfunction "VINA_1") (pintype "bidirectional"))
    )
    (net (code "23") (name "Net-(C28-P$1)") (class "Default")
      (node (ref "C28") (pin "1") (pinfunction "P$1_1") (pintype "passive"))
      (node (ref "R5") (pin "2") (pinfunction "2_2") (pintype "passive"))
      (node (ref "R6") (pin "1") (pinfunction "1_1") (pintype "passive"))
      (node (ref "U$3") (pin "3") (pinfunction "FB_3") (pintype "bidirectional"))
    )
    (net (code "24") (name "Net-(C36-P$2)") (class "Default")
      (node (ref "C36") (pin "2") (pinfunction "P$2_2") (pintype "passive"))
      (node (ref "U$3") (pin "1") (pinfunction "VINA_1") (pintype "bidirectional"))
    )
    (net (code "25") (name "Net-(CONN2-Pad5)") (class "Default")
      (node (ref "CONN2") (pin "5") (pinfunction "5_5") (pintype "passive"))
      (node (ref "U$1") (pin "8") (pinfunction "8_8") (pintype "bidirectional"))
      (node (ref "U$1") (pin "P$8") (pinfunction "8_P$8") (pintype "bidirectional"))
    )
    (net (code "26") (name "Net-(CONN2-Pad6)") (class "Default")
      (node (ref "CONN2") (pin "6") (pinfunction "6_6") (pintype "passive"))
      (node (ref "U$1") (pin "7") (pinfunction "7_7") (pintype "bidirectional"))
      (node (ref "U$1") (pin "P$7") (pinfunction "7_P$7") (pintype "bidirectional"))
    )
    (net (code "27") (name "Net-(D5-PadA)") (class "Default")
      (node (ref "D5") (pin "A") (pinfunction "A_A") (pintype "passive"))
      (node (ref "R44") (pin "1") (pinfunction "1_1") (pintype "passive"))
    )
    (net (code "28") (name "Net-(L1-1)") (class "Default")
      (node (ref "L1") (pin "P$1") (pinfunction "1_P$1") (pintype "passive"))
      (node (ref "U$2") (pin "8") (pinfunction "L1_2_8") (pintype "bidirectional"))
      (node (ref "U$2") (pin "9") (pinfunction "L1_1_9") (pintype "bidirectional"))
    )
    (net (code "29") (name "Net-(L1-2)") (class "Default")
      (node (ref "L1") (pin "P$2") (pinfunction "2_P$2") (pintype "passive"))
      (node (ref "U$2") (pin "6") (pinfunction "L2_1_6") (pintype "bidirectional"))
      (node (ref "U$2") (pin "7") (pinfunction "L2_2_7") (pintype "bidirectional"))
    )
    (net (code "30") (name "Net-(L3-1)") (class "Default")
      (node (ref "L3") (pin "P$1") (pinfunction "1_P$1") (pintype "passive"))
      (node (ref "U$3") (pin "8") (pinfunction "L1_2_8") (pintype "bidirectional"))
      (node (ref "U$3") (pin "9") (pinfunction "L1_1_9") (pintype "bidirectional"))
    )
    (net (code "31") (name "Net-(L3-2)") (class "Default")
      (node (ref "L3") (pin "P$2") (pinfunction "2_P$2") (pintype "passive"))
      (node (ref "U$3") (pin "6") (pinfunction "L2_1_6") (pintype "bidirectional"))
      (node (ref "U$3") (pin "7") (pinfunction "L2_2_7") (pintype "bidirectional"))
    )
    (net (code "32") (name "Net-(R4-Pad1)") (class "Default")
      (node (ref "R4") (pin "1") (pinfunction "1_1") (pintype "passive"))
      (node (ref "R6") (pin "2") (pinfunction "2_2") (pintype "passive"))
    )
    (net (code "33") (name "Net-(R11-Pad1)") (class "Default")
      (node (ref "R11") (pin "1") (pinfunction "1_1") (pintype "passive"))
      (node (ref "R44") (pin "2") (pinfunction "2_2") (pintype "passive"))
    )
    (net (code "34") (name "Net-(R17-Pad2)") (class "Default")
      (node (ref "R17") (pin "2") (pinfunction "2_2") (pintype "passive"))
      (node (ref "R8") (pin "1") (pinfunction "1_1") (pintype "passive"))
    )
    (net (code "35") (name "Net-(U$2-EN)") (class "Default")
      (node (ref "R14") (pin "2") (pinfunction "2_2") (pintype "passive"))
      (node (ref "R15") (pin "1") (pinfunction "1_1") (pintype "passive"))
      (node (ref "R27") (pin "1") (pinfunction "1_1") (pintype "passive"))
      (node (ref "U$2") (pin "12") (pinfunction "EN_12") (pintype "bidirectional"))
    )
    (net (code "36") (name "Net-(U$2-PG)") (class "Default")
      (node (ref "R12") (pin "2") (pinfunction "2_2") (pintype "passive"))
      (node (ref "R13") (pin "1") (pinfunction "1_1") (pintype "passive"))
      (node (ref "R25") (pin "1") (pinfunction "1_1") (pintype "passive"))
      (node (ref "U$2") (pin "14") (pinfunction "PG_14") (pintype "bidirectional"))
    )
    (net (code "37") (name "Net-(U$2-PS)") (class "Default")
      (node (ref "R16") (pin "2") (pinfunction "2_2") (pintype "passive"))
      (node (ref "R18") (pin "1") (pinfunction "1_1") (pintype "passive"))
      (node (ref "U$2") (pin "13") (pinfunction "PS_13") (pintype "bidirectional"))
    )
    (net (code "38") (name "Net-(U$3-EN)") (class "Default")
      (node (ref "R21") (pin "2") (pinfunction "2_2") (pintype "passive"))
      (node (ref "R22") (pin "1") (pinfunction "1_1") (pintype "passive"))
      (node (ref "R28") (pin "1") (pinfunction "1_1") (pintype "passive"))
      (node (ref "U$3") (pin "12") (pinfunction "EN_12") (pintype "bidirectional"))
    )
    (net (code "39") (name "Net-(U$3-PG)") (class "Default")
      (node (ref "R19") (pin "2") (pinfunction "2_2") (pintype "passive"))
      (node (ref "R20") (pin "1") (pinfunction "1_1") (pintype "passive"))
      (node (ref "R26") (pin "1") (pinfunction "1_1") (pintype "passive"))
      (node (ref "U$3") (pin "14") (pinfunction "PG_14") (pintype "bidirectional"))
    )
    (net (code "40") (name "Net-(U$3-PS)") (class "Default")
      (node (ref "R23") (pin "2") (pinfunction "2_2") (pintype "passive"))
      (node (ref "R24") (pin "1") (pinfunction "1_1") (pintype "passive"))
      (node (ref "U$3") (pin "13") (pinfunction "PS_13") (pintype "bidirectional"))
    )
    (net (code "41") (name "Net-(U1-~{QON})") (class "Default")
      (node (ref "R1") (pin "1") (pinfunction "1_1") (pintype "passive"))
      (node (ref "U1") (pin "12") (pinfunction "~{QON}_12") (pintype "bidirectional"))
    )
    (net (code "42") (name "Net-(U4-CELL)") (class "Default")
      (node (ref "C6") (pin "1") (pinfunction "1_1") (pintype "bidirectional"))
      (node (ref "R54") (pin "2") (pinfunction "2_2") (pintype "passive"))
      (node (ref "U4") (pin "2") (pinfunction "CELL_2") (pintype "bidirectional"))
    )
    (net (code "43") (name "Net-(U4-VDD)") (class "Default")
      (node (ref "C5") (pin "1") (pinfunction "1_1") (pintype "bidirectional"))
      (node (ref "R7") (pin "2") (pinfunction "2_2") (pintype "passive"))
      (node (ref "U4") (pin "3") (pinfunction "VDD_3") (pintype "bidirectional"))
    )
    (net (code "44") (name "VBAT") (class "Default")
      (node (ref "C3") (pin "1") (pinfunction "1_1") (pintype "bidirectional"))
      (node (ref "C72") (pin "1") (pinfunction "1_1") (pintype "bidirectional"))
      (node (ref "C73") (pin "1") (pinfunction "1_1") (pintype "bidirectional"))
      (node (ref "CONN1") (pin "5") (pinfunction "5_5") (pintype "passive"))
      (node (ref "CONN1") (pin "6") (pinfunction "6_6") (pintype "passive"))
      (node (ref "CONN1") (pin "7") (pinfunction "7_7") (pintype "passive"))
      (node (ref "R54") (pin "1") (pinfunction "1_1") (pintype "passive"))
      (node (ref "U$4") (pin "5") (pinfunction "5_5") (pintype "bidirectional"))
      (node (ref "U$4") (pin "6") (pinfunction "6_6") (pintype "bidirectional"))
      (node (ref "U$4") (pin "7") (pinfunction "7_7") (pintype "bidirectional"))
      (node (ref "U$4") (pin "P$5") (pinfunction "5_P$5") (pintype "bidirectional"))
      (node (ref "U$4") (pin "P$6") (pinfunction "6_P$6") (pintype "bidirectional"))
      (node (ref "U$4") (pin "P$7") (pinfunction "7_P$7") (pintype "bidirectional"))
      (node (ref "U1") (pin "13") (pinfunction "BAT_13") (pintype "passive"))
      (node (ref "U1") (pin "14") (pinfunction "BAT_14") (pintype "power_in"))
    )
    (net (code "45") (name "VCC") (class "Default")
      (node (ref "CONN2") (pin "7") (pinfunction "7_7") (pintype "passive"))
      (node (ref "CONN2") (pin "8") (pinfunction "8_8") (pintype "passive"))
      (node (ref "L14") (pin "1") (pinfunction "1_1") (pintype "bidirectional"))
      (node (ref "R11") (pin "2") (pinfunction "2_2") (pintype "passive"))
      (node (ref "U$1") (pin "5") (pinfunction "5_5") (pintype "bidirectional"))
      (node (ref "U$1") (pin "6") (pinfunction "6_6") (pintype "bidirectional"))
      (node (ref "U$1") (pin "P$5") (pinfunction "5_P$5") (pintype "bidirectional"))
      (node (ref "U$1") (pin "P$6") (pinfunction "6_P$6") (pintype "bidirectional"))
    )
    (net (code "46") (name "VSYS") (class "Default")
      (node (ref "C1") (pin "2") (pinfunction "P$2_2") (pintype "passive"))
      (node (ref "C12") (pin "1") (pinfunction "1_1") (pintype "bidirectional"))
      (node (ref "C13") (pin "2") (pinfunction "P$2_2") (pintype "passive"))
      (node (ref "C21") (pin "2") (pinfunction "P$2_2") (pintype "passive"))
      (node (ref "C22") (pin "1") (pinfunction "1_1") (pintype "bidirectional"))
      (node (ref "C26") (pin "1") (pinfunction "1_1") (pintype "bidirectional"))
      (node (ref "C27") (pin "2") (pinfunction "P$2_2") (pintype "passive"))
      (node (ref "C33") (pin "1") (pinfunction "1_1") (pintype "bidirectional"))
      (node (ref "C4") (pin "2") (pinfunction "P$2_2") (pintype "passive"))
      (node (ref "C58") (pin "1") (pinfunction "1_1") (pintype "bidirectional"))
      (node (ref "C59") (pin "1") (pinfunction "1_1") (pintype "bidirectional"))
      (node (ref "C8") (pin "2") (pinfunction "P$2_2") (pintype "passive"))
      (node (ref "L7") (pin "P$2") (pinfunction "2_P$2") (pintype "passive"))
      (node (ref "R14") (pin "1") (pinfunction "1_1") (pintype "passive"))
      (node (ref "R16") (pin "1") (pinfunction "1_1") (pintype "passive"))
      (node (ref "R21") (pin "1") (pinfunction "1_1") (pintype "passive"))
      (node (ref "R23") (pin "1") (pinfunction "1_1") (pintype "passive"))
      (node (ref "U$2") (pin "10") (pinfunction "VIN1_10") (pintype "bidirectional"))
      (node (ref "U$2") (pin "11") (pinfunction "VIN2_11") (pintype "bidirectional"))
      (node (ref "U$3") (pin "10") (pinfunction "VIN1_10") (pintype "bidirectional"))
      (node (ref "U$3") (pin "11") (pinfunction "VIN2_11") (pintype "bidirectional"))
      (node (ref "U1") (pin "15") (pinfunction "SYS_15") (pintype "power_in"))
      (node (ref "U1") (pin "16") (pinfunction "SYS_16") (pintype "power_in"))
    )
    (net (code "47") (name "unconnected-(U1-PSEL-Pad2)") (class "Default")
      (node (ref "U1") (pin "2") (pinfunction "PSEL_2") (pintype "output"))
    )
    (net (code "48") (name "unconnected-(U1-~{PG}-Pad3)") (class "Default")
      (node (ref "U1") (pin "3") (pinfunction "~{PG}_3") (pintype "output"))
    )
  )
)
